# Qwiic_Adaptive_Switch.net
KiCad netlist of a schematic drawn in EAGLE
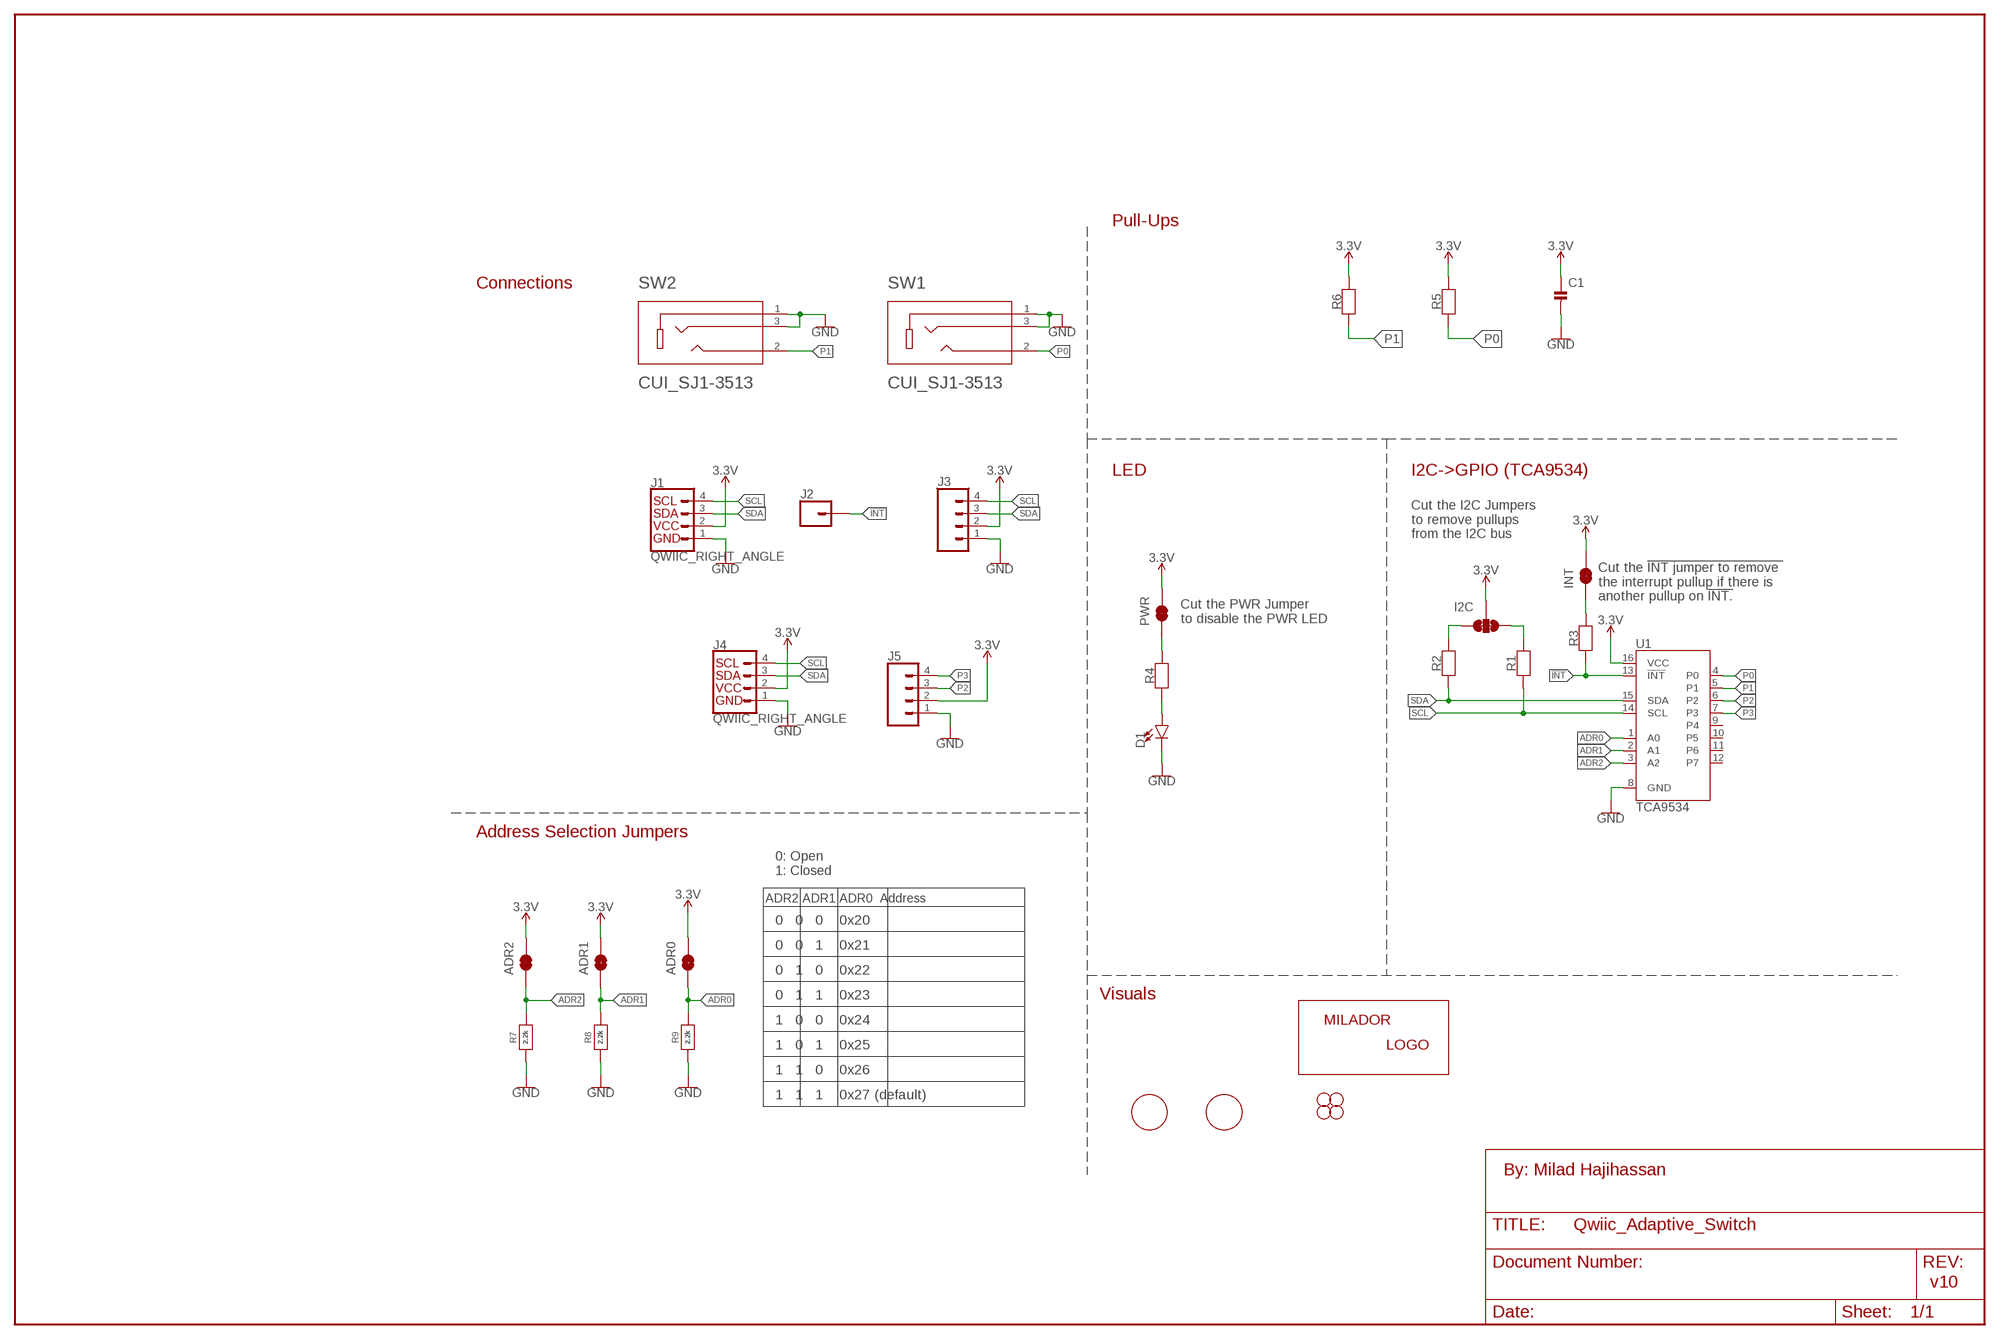
[diagram p0: schematic, sheet 1]

(export (version "E")
  (design (tool "Eeschema 10.0.6"))
  (components
    (comp (ref "ADR0")
      (value "JUMPERS-SMT_2_NC_TRACE_SILK")
      (footprint "eagle-import:JUMPERS_SMT-JUMPER_2_NC_TRACE_SILK")
      (libsource (lib "eagle-import") (part "JUMPERS-SMT_2_NC_TRACE_SILK"))
    )
    (comp (ref "ADR1")
      (value "JUMPERS-SMT_2_NC_TRACE_SILK")
      (footprint "eagle-import:JUMPERS_SMT-JUMPER_2_NC_TRACE_SILK")
      (libsource (lib "eagle-import") (part "JUMPERS-SMT_2_NC_TRACE_SILK"))
    )
    (comp (ref "ADR2")
      (value "JUMPERS-SMT_2_NC_TRACE_SILK")
      (footprint "eagle-import:JUMPERS_SMT-JUMPER_2_NC_TRACE_SILK")
      (libsource (lib "eagle-import") (part "JUMPERS-SMT_2_NC_TRACE_SILK"))
    )
    (comp (ref "C1")
      (value "0.1uF")
      (footprint "eagle-import:0603")
      (libsource (lib "eagle-import") (part "CAP_CERAMIC-0603"))
    )
    (comp (ref "D1")
      (value "RED")
      (footprint "eagle-import:LED-0603")
      (libsource (lib "eagle-import") (part "LED"))
    )
    (comp (ref "H1")
      (value "STAND-OFF")
      (footprint "eagle-import:STAND-OFF")
      (libsource (lib "eagle-import") (part "SparkFun-Hardware_STAND-OFF"))
    )
    (comp (ref "H2")
      (value "STAND-OFF")
      (footprint "eagle-import:STAND-OFF")
      (libsource (lib "eagle-import") (part "SparkFun-Hardware_STAND-OFF"))
    )
    (comp (ref "I2C")
      (value "JUMPERS_JUMPER-SMT_3_2-NC_TRACE_SILK")
      (footprint "eagle-import:JUMPERS_SMT-JUMPER_3_2-NC_TRACE_SILK")
      (libsource (lib "eagle-import") (part "JUMPERS_JUMPER-SMT_3_2-NC_TRACE_SILK"))
    )
    (comp (ref "INT")
      (value "JUMPERS-SMT_2_NC_TRACE_SILK")
      (footprint "eagle-import:JUMPERS_SMT-JUMPER_2_NC_TRACE_SILK")
      (libsource (lib "eagle-import") (part "JUMPERS-SMT_2_NC_TRACE_SILK"))
    )
    (comp (ref "J1")
      (value "QWIIC_RIGHT_ANGLE")
      (footprint "eagle-import:CONNECTORS_JST04_1MM_RA")
      (fields (field (name "PROD_ID") "CONN-13694"))
      (libsource (lib "eagle-import") (part "QWIIC_CONNECTORSJS-1MM"))
    )
    (comp (ref "J2")
      (value "CONNECTORS_CONN_01PTH_NO_SILK_YES_STOP")
      (footprint "eagle-import:CONNECTORS_1X01_NO_SILK")
      (libsource (lib "eagle-import") (part "CONNECTORS_CONN_01PTH_NO_SILK_YES_STOP"))
    )
    (comp (ref "J3")
      (value "CONNECTORS_CONN_041X04_NO_SILK")
      (footprint "eagle-import:CONNECTORS_1X04_NO_SILK")
      (libsource (lib "eagle-import") (part "CONNECTORS_CONN_041X04_NO_SILK"))
    )
    (comp (ref "J4")
      (value "QWIIC_RIGHT_ANGLE")
      (footprint "eagle-import:CONNECTORS_JST04_1MM_RA")
      (fields (field (name "PROD_ID") "CONN-13694"))
      (libsource (lib "eagle-import") (part "QWIIC_CONNECTORSJS-1MM"))
    )
    (comp (ref "J5")
      (value "CONNECTORS_CONN_041X04_NO_SILK")
      (footprint "eagle-import:CONNECTORS_1X04_NO_SILK")
      (libsource (lib "eagle-import") (part "CONNECTORS_CONN_041X04_NO_SILK"))
    )
    (comp (ref "JP3")
      (value "STAND-OFF")
      (footprint "eagle-import:STAND-OFF")
      (libsource (lib "eagle-import") (part "STAND-OFF"))
    )
    (comp (ref "JP4")
      (value "STAND-OFF")
      (footprint "eagle-import:STAND-OFF")
      (libsource (lib "eagle-import") (part "STAND-OFF"))
    )
    (comp (ref "PWR")
      (value "JUMPERS-SMT_2_NC_TRACE_SILK")
      (footprint "eagle-import:JUMPERS_SMT-JUMPER_2_NC_TRACE_SILK")
      (libsource (lib "eagle-import") (part "JUMPERS-SMT_2_NC_TRACE_SILK"))
    )
    (comp (ref "R1")
      (value "2.2k")
      (footprint "eagle-import:0603")
      (libsource (lib "eagle-import") (part "RESISTOR-0603"))
    )
    (comp (ref "R2")
      (value "2.2k")
      (footprint "eagle-import:0603")
      (libsource (lib "eagle-import") (part "RESISTOR-0603"))
    )
    (comp (ref "R3")
      (value "10k")
      (footprint "eagle-import:0603")
      (libsource (lib "eagle-import") (part "RESISTOR-0603"))
    )
    (comp (ref "R4")
      (value "1k")
      (footprint "eagle-import:0603")
      (libsource (lib "eagle-import") (part "RESISTOR-0603"))
    )
    (comp (ref "R5")
      (value "10k")
      (footprint "eagle-import:0603")
      (libsource (lib "eagle-import") (part "RESISTOR-0603"))
    )
    (comp (ref "R6")
      (value "10K")
      (footprint "eagle-import:0603")
      (libsource (lib "eagle-import") (part "RESISTOR-0603"))
    )
    (comp (ref "R7")
      (value "2.2k")
      (footprint "eagle-import:0603")
      (libsource (lib "eagle-import") (part "RESISTOR-0603"))
    )
    (comp (ref "R8")
      (value "2.2k")
      (footprint "eagle-import:0603")
      (libsource (lib "eagle-import") (part "RESISTOR-0603"))
    )
    (comp (ref "R9")
      (value "2.2k")
      (footprint "eagle-import:0603")
      (libsource (lib "eagle-import") (part "RESISTOR-0603"))
    )
    (comp (ref "SW1")
      (value "CUI_SJ1-3513")
      (footprint "eagle-import:CUI_SJ1-3513")
      (libsource (lib "eagle-import") (part "CUI_SJ1-3513"))
    )
    (comp (ref "SW2")
      (value "CUI_SJ1-3513")
      (footprint "eagle-import:CUI_SJ1-3513")
      (libsource (lib "eagle-import") (part "CUI_SJ1-3513"))
    )
    (comp (ref "U$6")
      (value "MILADOR-LOGO-")
      (footprint "eagle-import:MILADOR_LOGO1")
      (libsource (lib "eagle-import") (part "MILADOR-LOGO-"))
    )
    (comp (ref "U$17")
      (value "MILADOR-SWITCH-NAME-SW1")
      (footprint "eagle-import:SWITCH-SW1")
      (libsource (lib "eagle-import") (part "MILADOR-SWITCH-NAME-SW1"))
    )
    (comp (ref "U$18")
      (value "MILADOR-SWITCH-NAME-SW2")
      (footprint "eagle-import:SWITCH-SW2")
      (libsource (lib "eagle-import") (part "MILADOR-SWITCH-NAME-SW2"))
    )
    (comp (ref "U1")
      (value "TCA9534")
      (footprint "eagle-import:16SOIC")
      (libsource (lib "eagle-import") (part "TCA9534U"))
    )
  )
  (nets
    (net (code "1") (name "/~{INT}") (class "Default")
      (node (ref "J2") (pin "1") (pinfunction "1_1") (pintype "passive"))
      (node (ref "R3") (pin "1") (pinfunction "1_1") (pintype "passive"))
      (node (ref "U1") (pin "13") (pinfunction "~{INT}_13") (pintype "bidirectional"))
    )
    (net (code "2") (name "3.3V") (class "Default")
      (node (ref "ADR0") (pin "2") (pinfunction "2_2") (pintype "passive"))
      (node (ref "ADR1") (pin "2") (pinfunction "2_2") (pintype "passive"))
      (node (ref "ADR2") (pin "2") (pinfunction "2_2") (pintype "passive"))
      (node (ref "C1") (pin "1") (pinfunction "1_1") (pintype "passive"))
      (node (ref "I2C") (pin "2") (pinfunction "2_2") (pintype "passive"))
      (node (ref "INT") (pin "2") (pinfunction "2_2") (pintype "passive"))
      (node (ref "J1") (pin "2") (pinfunction "2_2") (pintype "power_in"))
      (node (ref "J3") (pin "2") (pinfunction "2_2") (pintype "passive"))
      (node (ref "J4") (pin "2") (pinfunction "2_2") (pintype "power_in"))
      (node (ref "J5") (pin "2") (pinfunction "2_2") (pintype "passive"))
      (node (ref "PWR") (pin "2") (pinfunction "2_2") (pintype "passive"))
      (node (ref "R5") (pin "2") (pinfunction "2_2") (pintype "passive"))
      (node (ref "R6") (pin "2") (pinfunction "2_2") (pintype "passive"))
      (node (ref "U1") (pin "16") (pinfunction "VCC_16") (pintype "bidirectional"))
    )
    (net (code "3") (name "ADR0") (class "Default")
      (node (ref "ADR0") (pin "1") (pinfunction "1_1") (pintype "passive"))
      (node (ref "R9") (pin "2") (pinfunction "2_2") (pintype "passive"))
      (node (ref "U1") (pin "1") (pinfunction "A0_1") (pintype "bidirectional"))
    )
    (net (code "4") (name "ADR1") (class "Default")
      (node (ref "ADR1") (pin "1") (pinfunction "1_1") (pintype "passive"))
      (node (ref "R8") (pin "2") (pinfunction "2_2") (pintype "passive"))
      (node (ref "U1") (pin "2") (pinfunction "A1_2") (pintype "bidirectional"))
    )
    (net (code "5") (name "ADR2") (class "Default")
      (node (ref "ADR2") (pin "1") (pinfunction "1_1") (pintype "passive"))
      (node (ref "R7") (pin "2") (pinfunction "2_2") (pintype "passive"))
      (node (ref "U1") (pin "3") (pinfunction "A2_3") (pintype "bidirectional"))
    )
    (net (code "6") (name "GND") (class "Default")
      (node (ref "C1") (pin "2") (pinfunction "2_2") (pintype "passive"))
      (node (ref "D1") (pin "C") (pinfunction "C_C") (pintype "passive"))
      (node (ref "J1") (pin "1") (pinfunction "1_1") (pintype "power_in"))
      (node (ref "J3") (pin "1") (pinfunction "1_1") (pintype "passive"))
      (node (ref "J4") (pin "1") (pinfunction "1_1") (pintype "power_in"))
      (node (ref "J5") (pin "1") (pinfunction "1_1") (pintype "passive"))
      (node (ref "R7") (pin "1") (pinfunction "1_1") (pintype "passive"))
      (node (ref "R8") (pin "1") (pinfunction "1_1") (pintype "passive"))
      (node (ref "R9") (pin "1") (pinfunction "1_1") (pintype "passive"))
      (node (ref "SW1") (pin "1") (pinfunction "1_1") (pintype "passive"))
      (node (ref "SW1") (pin "3") (pinfunction "3_3") (pintype "passive"))
      (node (ref "SW2") (pin "1") (pinfunction "1_1") (pintype "passive"))
      (node (ref "SW2") (pin "3") (pinfunction "3_3") (pintype "passive"))
      (node (ref "U1") (pin "8") (pinfunction "GND_8") (pintype "bidirectional"))
    )
    (net (code "7") (name "Net-(D1-PadA)") (class "Default")
      (node (ref "D1") (pin "A") (pinfunction "A_A") (pintype "passive"))
      (node (ref "R4") (pin "1") (pinfunction "1_1") (pintype "passive"))
    )
    (net (code "8") (name "Net-(I2C-Pad1)") (class "Default")
      (node (ref "I2C") (pin "1") (pinfunction "1_1") (pintype "passive"))
      (node (ref "R2") (pin "2") (pinfunction "2_2") (pintype "passive"))
    )
    (net (code "9") (name "Net-(I2C-Pad3)") (class "Default")
      (node (ref "I2C") (pin "3") (pinfunction "3_3") (pintype "passive"))
      (node (ref "R1") (pin "2") (pinfunction "2_2") (pintype "passive"))
    )
    (net (code "10") (name "Net-(INT-Pad1)") (class "Default")
      (node (ref "INT") (pin "1") (pinfunction "1_1") (pintype "passive"))
      (node (ref "R3") (pin "2") (pinfunction "2_2") (pintype "passive"))
    )
    (net (code "11") (name "Net-(PWR-Pad1)") (class "Default")
      (node (ref "PWR") (pin "1") (pinfunction "1_1") (pintype "passive"))
      (node (ref "R4") (pin "2") (pinfunction "2_2") (pintype "passive"))
    )
    (net (code "12") (name "P0") (class "Default")
      (node (ref "R5") (pin "1") (pinfunction "1_1") (pintype "passive"))
      (node (ref "SW1") (pin "2") (pinfunction "2_2") (pintype "passive"))
      (node (ref "U1") (pin "4") (pinfunction "P0_4") (pintype "bidirectional"))
    )
    (net (code "13") (name "P1") (class "Default")
      (node (ref "R6") (pin "1") (pinfunction "1_1") (pintype "passive"))
      (node (ref "SW2") (pin "2") (pinfunction "2_2") (pintype "passive"))
      (node (ref "U1") (pin "5") (pinfunction "P1_5") (pintype "bidirectional"))
    )
    (net (code "14") (name "P2") (class "Default")
      (node (ref "J5") (pin "3") (pinfunction "3_3") (pintype "passive"))
      (node (ref "U1") (pin "6") (pinfunction "P2_6") (pintype "bidirectional"))
    )
    (net (code "15") (name "P3") (class "Default")
      (node (ref "J5") (pin "4") (pinfunction "4_4") (pintype "passive"))
      (node (ref "U1") (pin "7") (pinfunction "P3_7") (pintype "bidirectional"))
    )
    (net (code "16") (name "SCL") (class "Default")
      (node (ref "J1") (pin "4") (pinfunction "4_4") (pintype "passive"))
      (node (ref "J3") (pin "4") (pinfunction "4_4") (pintype "passive"))
      (node (ref "J4") (pin "4") (pinfunction "4_4") (pintype "passive"))
      (node (ref "R1") (pin "1") (pinfunction "1_1") (pintype "passive"))
      (node (ref "U1") (pin "14") (pinfunction "SCL_14") (pintype "bidirectional"))
    )
    (net (code "17") (name "SDA") (class "Default")
      (node (ref "J1") (pin "3") (pinfunction "3_3") (pintype "passive"))
      (node (ref "J3") (pin "3") (pinfunction "3_3") (pintype "passive"))
      (node (ref "J4") (pin "3") (pinfunction "3_3") (pintype "passive"))
      (node (ref "R2") (pin "1") (pinfunction "1_1") (pintype "passive"))
      (node (ref "U1") (pin "15") (pinfunction "SDA_15") (pintype "bidirectional"))
    )
    (net (code "18") (name "unconnected-(U1-P4-Pad9)") (class "Default")
      (node (ref "U1") (pin "9") (pinfunction "P4_9") (pintype "bidirectional"))
    )
    (net (code "19") (name "unconnected-(U1-P5-Pad10)") (class "Default")
      (node (ref "U1") (pin "10") (pinfunction "P5_10") (pintype "bidirectional"))
    )
    (net (code "20") (name "unconnected-(U1-P6-Pad11)") (class "Default")
      (node (ref "U1") (pin "11") (pinfunction "P6_11") (pintype "bidirectional"))
    )
    (net (code "21") (name "unconnected-(U1-P7-Pad12)") (class "Default")
      (node (ref "U1") (pin "12") (pinfunction "P7_12") (pintype "bidirectional"))
    )
  )
)
